# 2024-08-19.net
KiCad netlist of a schematic drawn in Altium Designer
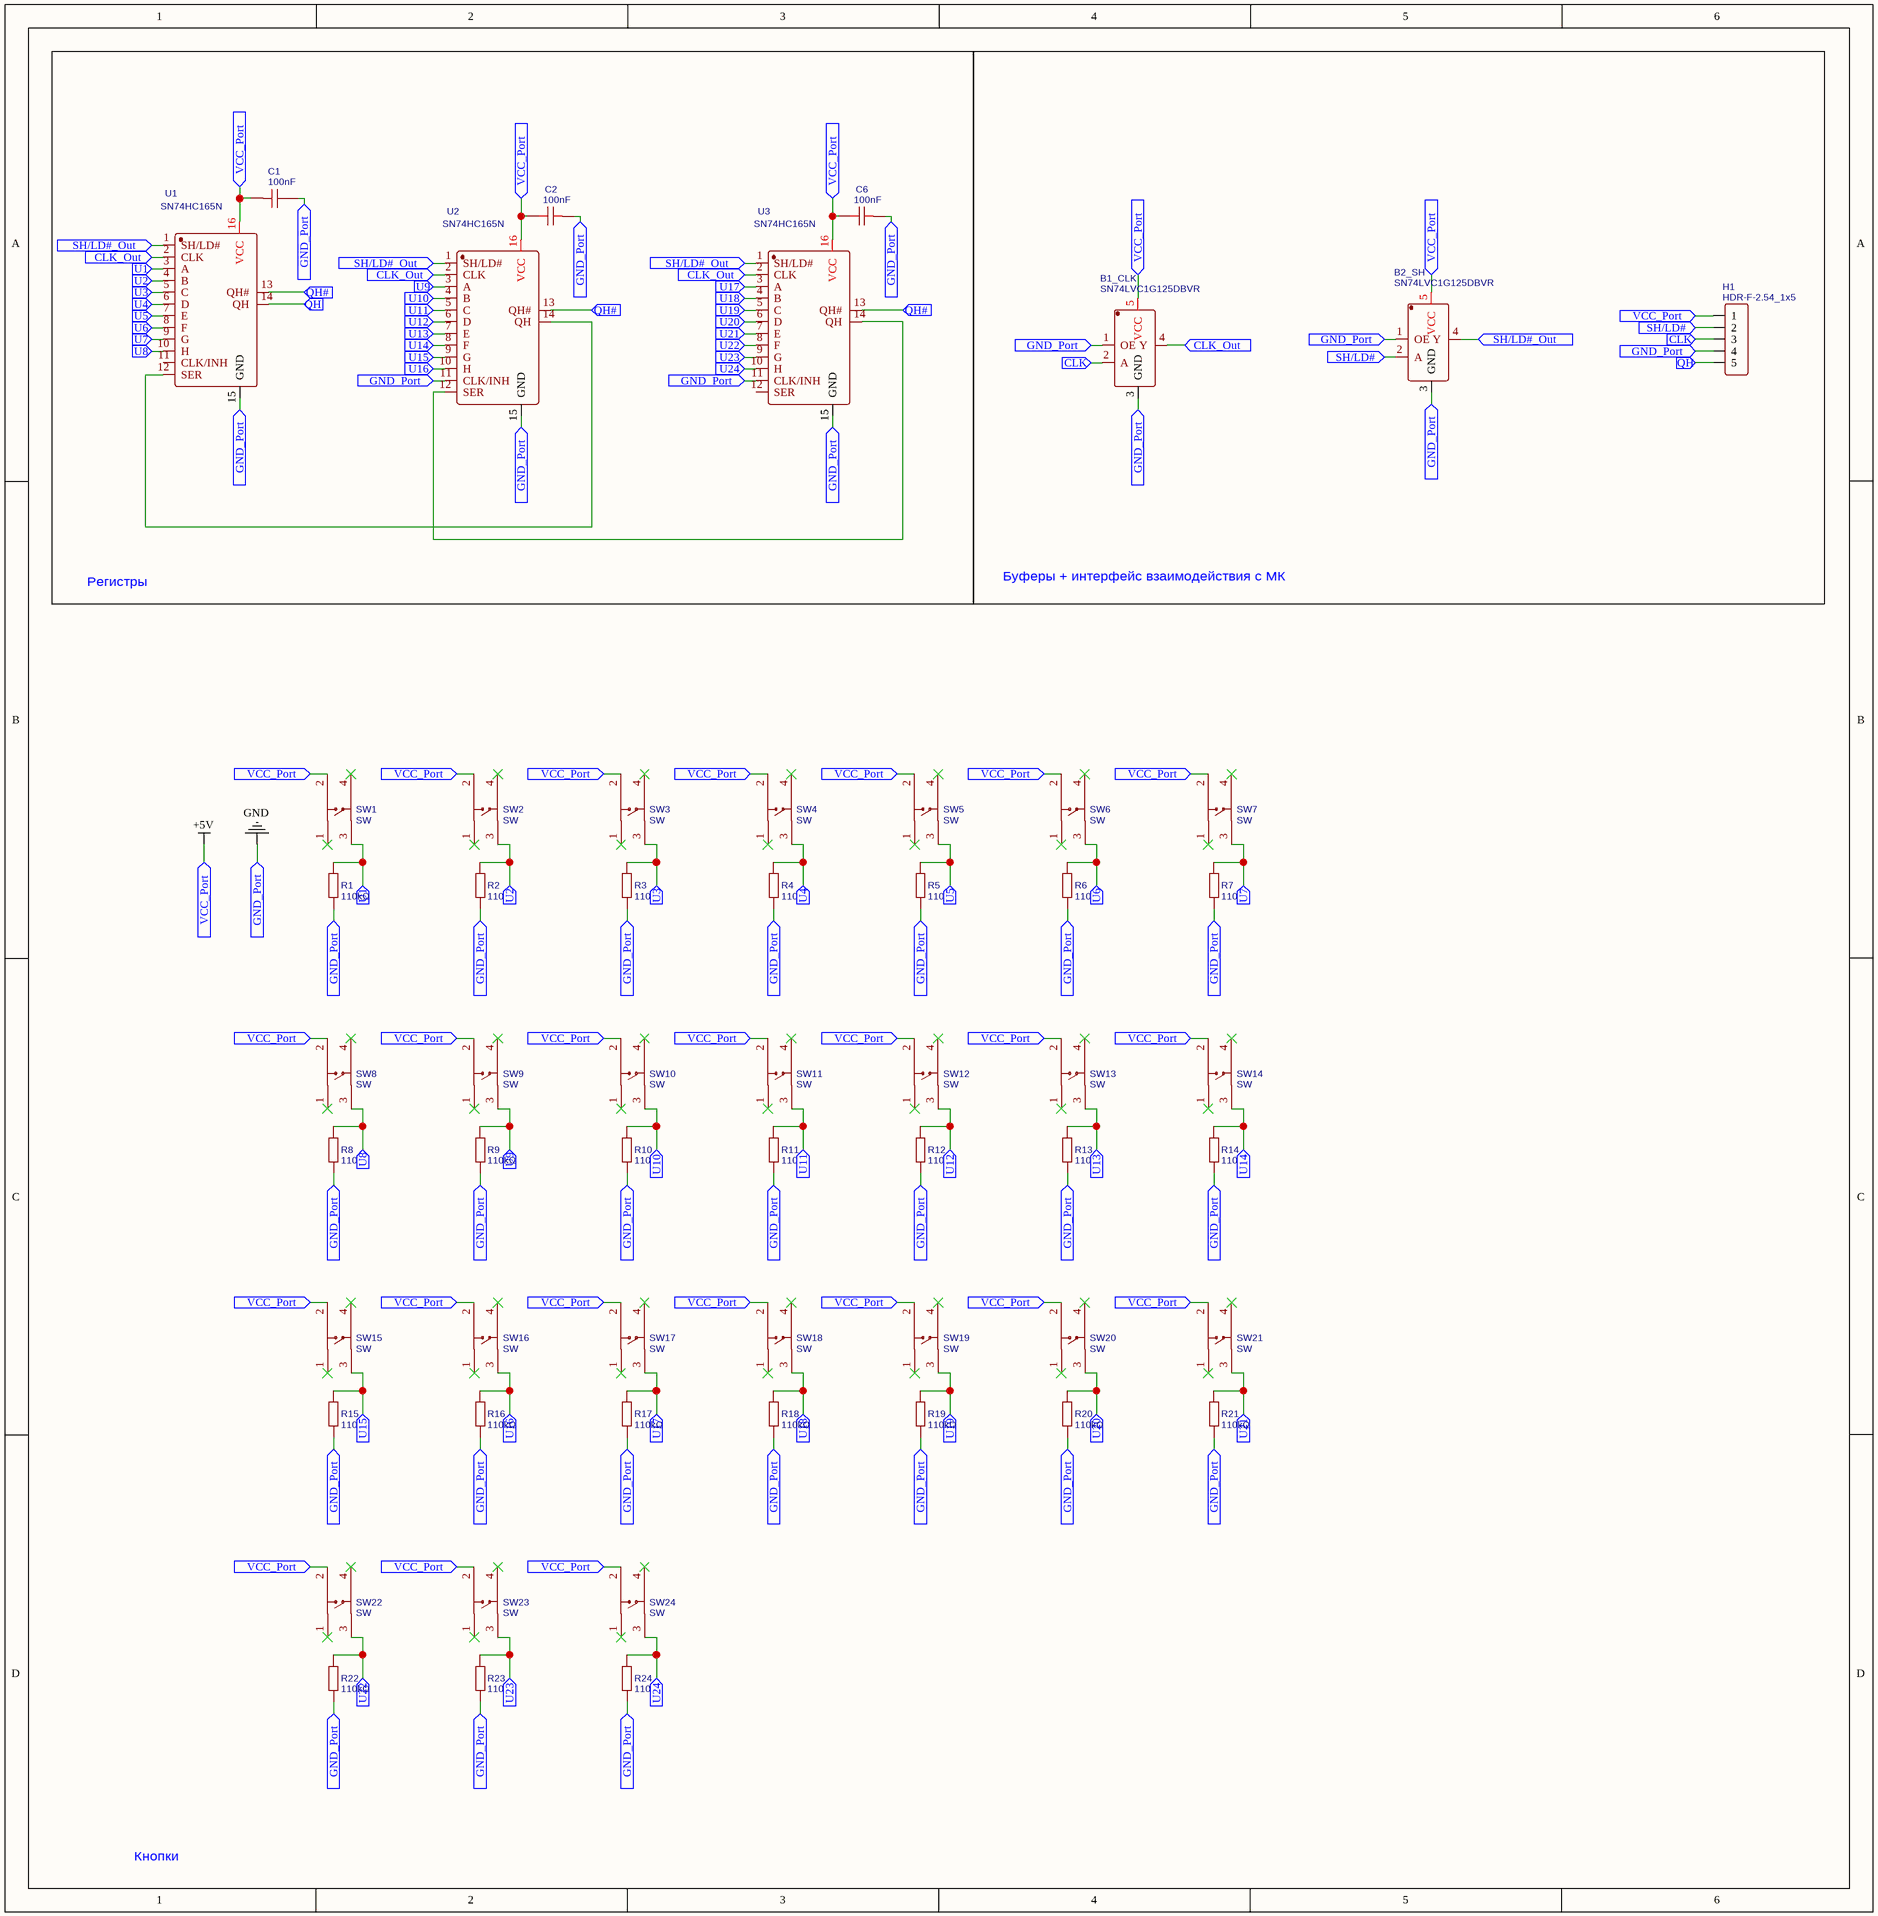
[diagram p0: Кнопки_2024-08-19.schdoc]

(export (version "E")
  (design (tool "Eeschema 10.0.6"))
  (components
    (comp (ref "B1_CLK")
      (value "SN74LVC1G125DBVR")
      (fields (field (name "MANUFACTURER") "TI(德州仪器)") (field (name "CONTRIBUTOR") "danik_mus"))
      (libsource (lib "altium-import") (part "root_0_SN74LVC1G125DBVR_"))
    )
    (comp (ref "B2_SH")
      (value "SN74LVC1G125DBVR")
      (fields (field (name "MANUFACTURER") "TI(德州仪器)") (field (name "CONTRIBUTOR") "danik_mus"))
      (libsource (lib "altium-import") (part "root_0_SN74LVC1G125DBVR_"))
    )
    (comp (ref "C1")
      (value "100nF")
      (fields
        (field (name "MANUFACTURER") "KYET(科雅)")
        (field (name "MANUFACTURER PART") "PE104J2A0504")
        (field (name "CONTRIBUTOR") "lcsc")
      )
      (libsource (lib "altium-import") (part "root_0_100nF_"))
    )
    (comp (ref "C2")
      (value "100nF")
      (fields
        (field (name "MANUFACTURER") "KYET(科雅)")
        (field (name "MANUFACTURER PART") "PE104J2A0504")
        (field (name "CONTRIBUTOR") "lcsc")
      )
      (libsource (lib "altium-import") (part "root_2_100nF_"))
    )
    (comp (ref "C6")
      (value "100nF")
      (fields
        (field (name "MANUFACTURER") "KYET(科雅)")
        (field (name "MANUFACTURER PART") "PE104J2A0504")
        (field (name "CONTRIBUTOR") "lcsc")
      )
      (libsource (lib "altium-import") (part "root_2_100nF_"))
    )
    (comp (ref "H1")
      (value "HDR-F-2.54_1x5")
      (fields (field (name "CONTRIBUTOR") "LCEDA_Lib"))
      (libsource (lib "altium-import") (part "root_0_HDR-F-2.54_1x5_"))
    )
    (comp (ref "R1")
      (value "110kΩ")
      (fields
        (field (name "MANUFACTURER") "CCO(千志电子)")
        (field (name "MANUFACTURER PART") "CF1/4W-110KΩ±5% T52")
        (field (name "CONTRIBUTOR") "LCSC")
      )
      (libsource (lib "altium-import") (part "root_3_110kΩ_"))
    )
    (comp (ref "R2")
      (value "110kΩ")
      (fields
        (field (name "MANUFACTURER") "CCO(千志电子)")
        (field (name "MANUFACTURER PART") "CF1/4W-110KΩ±5% T52")
        (field (name "CONTRIBUTOR") "LCSC")
      )
      (libsource (lib "altium-import") (part "root_3_110kΩ_"))
    )
    (comp (ref "R3")
      (value "110kΩ")
      (fields
        (field (name "MANUFACTURER") "CCO(千志电子)")
        (field (name "MANUFACTURER PART") "CF1/4W-110KΩ±5% T52")
        (field (name "CONTRIBUTOR") "LCSC")
      )
      (libsource (lib "altium-import") (part "root_3_110kΩ_"))
    )
    (comp (ref "R4")
      (value "110kΩ")
      (fields
        (field (name "MANUFACTURER") "CCO(千志电子)")
        (field (name "MANUFACTURER PART") "CF1/4W-110KΩ±5% T52")
        (field (name "CONTRIBUTOR") "LCSC")
      )
      (libsource (lib "altium-import") (part "root_3_110kΩ_"))
    )
    (comp (ref "R5")
      (value "110kΩ")
      (fields
        (field (name "MANUFACTURER") "CCO(千志电子)")
        (field (name "MANUFACTURER PART") "CF1/4W-110KΩ±5% T52")
        (field (name "CONTRIBUTOR") "LCSC")
      )
      (libsource (lib "altium-import") (part "root_3_110kΩ_"))
    )
    (comp (ref "R6")
      (value "110kΩ")
      (fields
        (field (name "MANUFACTURER") "CCO(千志电子)")
        (field (name "MANUFACTURER PART") "CF1/4W-110KΩ±5% T52")
        (field (name "CONTRIBUTOR") "LCSC")
      )
      (libsource (lib "altium-import") (part "root_3_110kΩ_"))
    )
    (comp (ref "R7")
      (value "110kΩ")
      (fields
        (field (name "MANUFACTURER") "CCO(千志电子)")
        (field (name "MANUFACTURER PART") "CF1/4W-110KΩ±5% T52")
        (field (name "CONTRIBUTOR") "LCSC")
      )
      (libsource (lib "altium-import") (part "root_3_110kΩ_"))
    )
    (comp (ref "R8")
      (value "110kΩ")
      (fields
        (field (name "MANUFACTURER") "CCO(千志电子)")
        (field (name "MANUFACTURER PART") "CF1/4W-110KΩ±5% T52")
        (field (name "CONTRIBUTOR") "LCSC")
      )
      (libsource (lib "altium-import") (part "root_3_110kΩ_"))
    )
    (comp (ref "R9")
      (value "110kΩ")
      (fields
        (field (name "MANUFACTURER") "CCO(千志电子)")
        (field (name "MANUFACTURER PART") "CF1/4W-110KΩ±5% T52")
        (field (name "CONTRIBUTOR") "LCSC")
      )
      (libsource (lib "altium-import") (part "root_3_110kΩ_"))
    )
    (comp (ref "R10")
      (value "110kΩ")
      (fields
        (field (name "MANUFACTURER") "CCO(千志电子)")
        (field (name "MANUFACTURER PART") "CF1/4W-110KΩ±5% T52")
        (field (name "CONTRIBUTOR") "LCSC")
      )
      (libsource (lib "altium-import") (part "root_3_110kΩ_"))
    )
    (comp (ref "R11")
      (value "110kΩ")
      (fields
        (field (name "MANUFACTURER") "CCO(千志电子)")
        (field (name "MANUFACTURER PART") "CF1/4W-110KΩ±5% T52")
        (field (name "CONTRIBUTOR") "LCSC")
      )
      (libsource (lib "altium-import") (part "root_3_110kΩ_"))
    )
    (comp (ref "R12")
      (value "110kΩ")
      (fields
        (field (name "MANUFACTURER") "CCO(千志电子)")
        (field (name "MANUFACTURER PART") "CF1/4W-110KΩ±5% T52")
        (field (name "CONTRIBUTOR") "LCSC")
      )
      (libsource (lib "altium-import") (part "root_3_110kΩ_"))
    )
    (comp (ref "R13")
      (value "110kΩ")
      (fields
        (field (name "MANUFACTURER") "CCO(千志电子)")
        (field (name "MANUFACTURER PART") "CF1/4W-110KΩ±5% T52")
        (field (name "CONTRIBUTOR") "LCSC")
      )
      (libsource (lib "altium-import") (part "root_3_110kΩ_"))
    )
    (comp (ref "R14")
      (value "110kΩ")
      (fields
        (field (name "MANUFACTURER") "CCO(千志电子)")
        (field (name "MANUFACTURER PART") "CF1/4W-110KΩ±5% T52")
        (field (name "CONTRIBUTOR") "LCSC")
      )
      (libsource (lib "altium-import") (part "root_3_110kΩ_"))
    )
    (comp (ref "R15")
      (value "110kΩ")
      (fields
        (field (name "MANUFACTURER") "CCO(千志电子)")
        (field (name "MANUFACTURER PART") "CF1/4W-110KΩ±5% T52")
        (field (name "CONTRIBUTOR") "LCSC")
      )
      (libsource (lib "altium-import") (part "root_3_110kΩ_"))
    )
    (comp (ref "R16")
      (value "110kΩ")
      (fields
        (field (name "MANUFACTURER") "CCO(千志电子)")
        (field (name "MANUFACTURER PART") "CF1/4W-110KΩ±5% T52")
        (field (name "CONTRIBUTOR") "LCSC")
      )
      (libsource (lib "altium-import") (part "root_3_110kΩ_"))
    )
    (comp (ref "R17")
      (value "110kΩ")
      (fields
        (field (name "MANUFACTURER") "CCO(千志电子)")
        (field (name "MANUFACTURER PART") "CF1/4W-110KΩ±5% T52")
        (field (name "CONTRIBUTOR") "LCSC")
      )
      (libsource (lib "altium-import") (part "root_3_110kΩ_"))
    )
    (comp (ref "R18")
      (value "110kΩ")
      (fields
        (field (name "MANUFACTURER") "CCO(千志电子)")
        (field (name "MANUFACTURER PART") "CF1/4W-110KΩ±5% T52")
        (field (name "CONTRIBUTOR") "LCSC")
      )
      (libsource (lib "altium-import") (part "root_3_110kΩ_"))
    )
    (comp (ref "R19")
      (value "110kΩ")
      (fields
        (field (name "MANUFACTURER") "CCO(千志电子)")
        (field (name "MANUFACTURER PART") "CF1/4W-110KΩ±5% T52")
        (field (name "CONTRIBUTOR") "LCSC")
      )
      (libsource (lib "altium-import") (part "root_3_110kΩ_"))
    )
    (comp (ref "R20")
      (value "110kΩ")
      (fields
        (field (name "MANUFACTURER") "CCO(千志电子)")
        (field (name "MANUFACTURER PART") "CF1/4W-110KΩ±5% T52")
        (field (name "CONTRIBUTOR") "LCSC")
      )
      (libsource (lib "altium-import") (part "root_3_110kΩ_"))
    )
    (comp (ref "R21")
      (value "110kΩ")
      (fields
        (field (name "MANUFACTURER") "CCO(千志电子)")
        (field (name "MANUFACTURER PART") "CF1/4W-110KΩ±5% T52")
        (field (name "CONTRIBUTOR") "LCSC")
      )
      (libsource (lib "altium-import") (part "root_3_110kΩ_"))
    )
    (comp (ref "R22")
      (value "110kΩ")
      (fields
        (field (name "MANUFACTURER") "CCO(千志电子)")
        (field (name "MANUFACTURER PART") "CF1/4W-110KΩ±5% T52")
        (field (name "CONTRIBUTOR") "LCSC")
      )
      (libsource (lib "altium-import") (part "root_3_110kΩ_"))
    )
    (comp (ref "R23")
      (value "110kΩ")
      (fields
        (field (name "MANUFACTURER") "CCO(千志电子)")
        (field (name "MANUFACTURER PART") "CF1/4W-110KΩ±5% T52")
        (field (name "CONTRIBUTOR") "LCSC")
      )
      (libsource (lib "altium-import") (part "root_3_110kΩ_"))
    )
    (comp (ref "R24")
      (value "110kΩ")
      (fields
        (field (name "MANUFACTURER") "CCO(千志电子)")
        (field (name "MANUFACTURER PART") "CF1/4W-110KΩ±5% T52")
        (field (name "CONTRIBUTOR") "LCSC")
      )
      (libsource (lib "altium-import") (part "root_3_110kΩ_"))
    )
    (comp (ref "SW1")
      (value "SW")
      (fields (field (name "MANUFACTURER PART") "按键") (field (name "CONTRIBUTOR") "lcsc"))
      (libsource (lib "altium-import") (part "root_1_SW_"))
    )
    (comp (ref "SW2")
      (value "SW")
      (fields (field (name "MANUFACTURER PART") "按键") (field (name "CONTRIBUTOR") "lcsc"))
      (libsource (lib "altium-import") (part "root_1_SW_"))
    )
    (comp (ref "SW3")
      (value "SW")
      (fields (field (name "MANUFACTURER PART") "按键") (field (name "CONTRIBUTOR") "lcsc"))
      (libsource (lib "altium-import") (part "root_1_SW_"))
    )
    (comp (ref "SW4")
      (value "SW")
      (fields (field (name "MANUFACTURER PART") "按键") (field (name "CONTRIBUTOR") "lcsc"))
      (libsource (lib "altium-import") (part "root_1_SW_"))
    )
    (comp (ref "SW5")
      (value "SW")
      (fields (field (name "MANUFACTURER PART") "按键") (field (name "CONTRIBUTOR") "lcsc"))
      (libsource (lib "altium-import") (part "root_1_SW_"))
    )
    (comp (ref "SW6")
      (value "SW")
      (fields (field (name "MANUFACTURER PART") "按键") (field (name "CONTRIBUTOR") "lcsc"))
      (libsource (lib "altium-import") (part "root_1_SW_"))
    )
    (comp (ref "SW7")
      (value "SW")
      (fields (field (name "MANUFACTURER PART") "按键") (field (name "CONTRIBUTOR") "lcsc"))
      (libsource (lib "altium-import") (part "root_1_SW_"))
    )
    (comp (ref "SW8")
      (value "SW")
      (fields (field (name "MANUFACTURER PART") "按键") (field (name "CONTRIBUTOR") "lcsc"))
      (libsource (lib "altium-import") (part "root_1_SW_"))
    )
    (comp (ref "SW9")
      (value "SW")
      (fields (field (name "MANUFACTURER PART") "按键") (field (name "CONTRIBUTOR") "lcsc"))
      (libsource (lib "altium-import") (part "root_1_SW_"))
    )
    (comp (ref "SW10")
      (value "SW")
      (fields (field (name "MANUFACTURER PART") "按键") (field (name "CONTRIBUTOR") "lcsc"))
      (libsource (lib "altium-import") (part "root_1_SW_"))
    )
    (comp (ref "SW11")
      (value "SW")
      (fields (field (name "MANUFACTURER PART") "按键") (field (name "CONTRIBUTOR") "lcsc"))
      (libsource (lib "altium-import") (part "root_1_SW_"))
    )
    (comp (ref "SW12")
      (value "SW")
      (fields (field (name "MANUFACTURER PART") "按键") (field (name "CONTRIBUTOR") "lcsc"))
      (libsource (lib "altium-import") (part "root_1_SW_"))
    )
    (comp (ref "SW13")
      (value "SW")
      (fields (field (name "MANUFACTURER PART") "按键") (field (name "CONTRIBUTOR") "lcsc"))
      (libsource (lib "altium-import") (part "root_1_SW_"))
    )
    (comp (ref "SW14")
      (value "SW")
      (fields (field (name "MANUFACTURER PART") "按键") (field (name "CONTRIBUTOR") "lcsc"))
      (libsource (lib "altium-import") (part "root_1_SW_"))
    )
    (comp (ref "SW15")
      (value "SW")
      (fields (field (name "MANUFACTURER PART") "按键") (field (name "CONTRIBUTOR") "lcsc"))
      (libsource (lib "altium-import") (part "root_1_SW_"))
    )
    (comp (ref "SW16")
      (value "SW")
      (fields (field (name "MANUFACTURER PART") "按键") (field (name "CONTRIBUTOR") "lcsc"))
      (libsource (lib "altium-import") (part "root_1_SW_"))
    )
    (comp (ref "SW17")
      (value "SW")
      (fields (field (name "MANUFACTURER PART") "按键") (field (name "CONTRIBUTOR") "lcsc"))
      (libsource (lib "altium-import") (part "root_1_SW_"))
    )
    (comp (ref "SW18")
      (value "SW")
      (fields (field (name "MANUFACTURER PART") "按键") (field (name "CONTRIBUTOR") "lcsc"))
      (libsource (lib "altium-import") (part "root_1_SW_"))
    )
    (comp (ref "SW19")
      (value "SW")
      (fields (field (name "MANUFACTURER PART") "按键") (field (name "CONTRIBUTOR") "lcsc"))
      (libsource (lib "altium-import") (part "root_1_SW_"))
    )
    (comp (ref "SW20")
      (value "SW")
      (fields (field (name "MANUFACTURER PART") "按键") (field (name "CONTRIBUTOR") "lcsc"))
      (libsource (lib "altium-import") (part "root_1_SW_"))
    )
    (comp (ref "SW21")
      (value "SW")
      (fields (field (name "MANUFACTURER PART") "按键") (field (name "CONTRIBUTOR") "lcsc"))
      (libsource (lib "altium-import") (part "root_1_SW_"))
    )
    (comp (ref "SW22")
      (value "SW")
      (fields (field (name "MANUFACTURER PART") "按键") (field (name "CONTRIBUTOR") "lcsc"))
      (libsource (lib "altium-import") (part "root_1_SW_"))
    )
    (comp (ref "SW23")
      (value "SW")
      (fields (field (name "MANUFACTURER PART") "按键") (field (name "CONTRIBUTOR") "lcsc"))
      (libsource (lib "altium-import") (part "root_1_SW_"))
    )
    (comp (ref "SW24")
      (value "SW")
      (fields (field (name "MANUFACTURER PART") "按键") (field (name "CONTRIBUTOR") "lcsc"))
      (libsource (lib "altium-import") (part "root_1_SW_"))
    )
    (comp (ref "U1")
      (value "SN74HC165N")
      (fields (field (name "MANUFACTURER") "TI(德州仪器)") (field (name "CONTRIBUTOR") "danik_mus"))
      (libsource (lib "altium-import") (part "root_0_SN74HC165N_"))
    )
    (comp (ref "U2")
      (value "SN74HC165N")
      (fields (field (name "MANUFACTURER") "TI(德州仪器)") (field (name "CONTRIBUTOR") "danik_mus"))
      (libsource (lib "altium-import") (part "root_0_SN74HC165N_"))
    )
    (comp (ref "U3")
      (value "SN74HC165N")
      (fields (field (name "MANUFACTURER") "TI(德州仪器)") (field (name "CONTRIBUTOR") "danik_mus"))
      (libsource (lib "altium-import") (part "root_0_SN74HC165N_"))
    )
  )
  (nets
    (net (code "1") (name "+5V") (class "Default")
      (node (ref "B1_CLK") (pin "5") (pinfunction "VCC_5") (pintype "passive"))
      (node (ref "B2_SH") (pin "5") (pinfunction "VCC_5") (pintype "passive"))
      (node (ref "C1") (pin "1") (pinfunction "1_1") (pintype "passive"))
      (node (ref "C2") (pin "2") (pinfunction "2_2") (pintype "passive"))
      (node (ref "C6") (pin "2") (pinfunction "2_2") (pintype "passive"))
      (node (ref "H1") (pin "1") (pinfunction "1_1") (pintype "passive"))
      (node (ref "SW1") (pin "2") (pinfunction "2_2") (pintype "passive"))
      (node (ref "SW10") (pin "2") (pinfunction "2_2") (pintype "passive"))
      (node (ref "SW11") (pin "2") (pinfunction "2_2") (pintype "passive"))
      (node (ref "SW12") (pin "2") (pinfunction "2_2") (pintype "passive"))
      (node (ref "SW13") (pin "2") (pinfunction "2_2") (pintype "passive"))
      (node (ref "SW14") (pin "2") (pinfunction "2_2") (pintype "passive"))
      (node (ref "SW15") (pin "2") (pinfunction "2_2") (pintype "passive"))
      (node (ref "SW16") (pin "2") (pinfunction "2_2") (pintype "passive"))
      (node (ref "SW17") (pin "2") (pinfunction "2_2") (pintype "passive"))
      (node (ref "SW18") (pin "2") (pinfunction "2_2") (pintype "passive"))
      (node (ref "SW19") (pin "2") (pinfunction "2_2") (pintype "passive"))
      (node (ref "SW2") (pin "2") (pinfunction "2_2") (pintype "passive"))
      (node (ref "SW20") (pin "2") (pinfunction "2_2") (pintype "passive"))
      (node (ref "SW21") (pin "2") (pinfunction "2_2") (pintype "passive"))
      (node (ref "SW22") (pin "2") (pinfunction "2_2") (pintype "passive"))
      (node (ref "SW23") (pin "2") (pinfunction "2_2") (pintype "passive"))
      (node (ref "SW24") (pin "2") (pinfunction "2_2") (pintype "passive"))
      (node (ref "SW3") (pin "2") (pinfunction "2_2") (pintype "passive"))
      (node (ref "SW4") (pin "2") (pinfunction "2_2") (pintype "passive"))
      (node (ref "SW5") (pin "2") (pinfunction "2_2") (pintype "passive"))
      (node (ref "SW6") (pin "2") (pinfunction "2_2") (pintype "passive"))
      (node (ref "SW7") (pin "2") (pinfunction "2_2") (pintype "passive"))
      (node (ref "SW8") (pin "2") (pinfunction "2_2") (pintype "passive"))
      (node (ref "SW9") (pin "2") (pinfunction "2_2") (pintype "passive"))
      (node (ref "U1") (pin "16") (pinfunction "VCC_16") (pintype "passive"))
      (node (ref "U2") (pin "16") (pinfunction "VCC_16") (pintype "passive"))
      (node (ref "U3") (pin "16") (pinfunction "VCC_16") (pintype "passive"))
    )
    (net (code "2") (name "/CLK") (class "Default")
      (node (ref "B1_CLK") (pin "2") (pinfunction "A_2") (pintype "passive"))
      (node (ref "H1") (pin "3") (pinfunction "3_3") (pintype "passive"))
    )
    (net (code "3") (name "/CLK_Out") (class "Default")
      (node (ref "B1_CLK") (pin "4") (pinfunction "Y_4") (pintype "passive"))
      (node (ref "U1") (pin "2") (pinfunction "CLK_2") (pintype "passive"))
      (node (ref "U2") (pin "2") (pinfunction "CLK_2") (pintype "passive"))
      (node (ref "U3") (pin "2") (pinfunction "CLK_2") (pintype "passive"))
    )
    (net (code "4") (name "/QH") (class "Default")
      (node (ref "H1") (pin "5") (pinfunction "5_5") (pintype "passive"))
      (node (ref "U1") (pin "14") (pinfunction "QH_14") (pintype "passive"))
    )
    (net (code "5") (name "/QH#") (class "Default")
      (node (ref "U1") (pin "13") (pinfunction "QH#_13") (pintype "passive"))
      (node (ref "U2") (pin "13") (pinfunction "QH#_13") (pintype "passive"))
      (node (ref "U3") (pin "13") (pinfunction "QH#_13") (pintype "passive"))
    )
    (net (code "6") (name "/SH{slash}LD#") (class "Default")
      (node (ref "B2_SH") (pin "2") (pinfunction "A_2") (pintype "passive"))
      (node (ref "H1") (pin "2") (pinfunction "2_2") (pintype "passive"))
    )
    (net (code "7") (name "/SH{slash}LD#_Out") (class "Default")
      (node (ref "B2_SH") (pin "4") (pinfunction "Y_4") (pintype "passive"))
      (node (ref "U1") (pin "1") (pinfunction "SH/LD#_1") (pintype "passive"))
      (node (ref "U2") (pin "1") (pinfunction "SH/LD#_1") (pintype "passive"))
      (node (ref "U3") (pin "1") (pinfunction "SH/LD#_1") (pintype "passive"))
    )
    (net (code "8") (name "/U1") (class "Default")
      (node (ref "R1") (pin "1") (pinfunction "1_1") (pintype "passive"))
      (node (ref "SW1") (pin "3") (pinfunction "3_3") (pintype "passive"))
      (node (ref "U1") (pin "3") (pinfunction "A_3") (pintype "passive"))
    )
    (net (code "9") (name "/U2") (class "Default")
      (node (ref "R2") (pin "1") (pinfunction "1_1") (pintype "passive"))
      (node (ref "SW2") (pin "3") (pinfunction "3_3") (pintype "passive"))
      (node (ref "U1") (pin "4") (pinfunction "B_4") (pintype "passive"))
    )
    (net (code "10") (name "/U3") (class "Default")
      (node (ref "R3") (pin "1") (pinfunction "1_1") (pintype "passive"))
      (node (ref "SW3") (pin "3") (pinfunction "3_3") (pintype "passive"))
      (node (ref "U1") (pin "5") (pinfunction "C_5") (pintype "passive"))
    )
    (net (code "11") (name "/U4") (class "Default")
      (node (ref "R4") (pin "1") (pinfunction "1_1") (pintype "passive"))
      (node (ref "SW4") (pin "3") (pinfunction "3_3") (pintype "passive"))
      (node (ref "U1") (pin "6") (pinfunction "D_6") (pintype "passive"))
    )
    (net (code "12") (name "/U5") (class "Default")
      (node (ref "R5") (pin "1") (pinfunction "1_1") (pintype "passive"))
      (node (ref "SW5") (pin "3") (pinfunction "3_3") (pintype "passive"))
      (node (ref "U1") (pin "7") (pinfunction "E_7") (pintype "passive"))
    )
    (net (code "13") (name "/U6") (class "Default")
      (node (ref "R6") (pin "1") (pinfunction "1_1") (pintype "passive"))
      (node (ref "SW6") (pin "3") (pinfunction "3_3") (pintype "passive"))
      (node (ref "U1") (pin "8") (pinfunction "F_8") (pintype "passive"))
    )
    (net (code "14") (name "/U7") (class "Default")
      (node (ref "R7") (pin "1") (pinfunction "1_1") (pintype "passive"))
      (node (ref "SW7") (pin "3") (pinfunction "3_3") (pintype "passive"))
      (node (ref "U1") (pin "9") (pinfunction "G_9") (pintype "passive"))
    )
    (net (code "15") (name "/U8") (class "Default")
      (node (ref "R8") (pin "1") (pinfunction "1_1") (pintype "passive"))
      (node (ref "SW8") (pin "3") (pinfunction "3_3") (pintype "passive"))
      (node (ref "U1") (pin "10") (pinfunction "H_10") (pintype "passive"))
    )
    (net (code "16") (name "/U9") (class "Default")
      (node (ref "R9") (pin "1") (pinfunction "1_1") (pintype "passive"))
      (node (ref "SW9") (pin "3") (pinfunction "3_3") (pintype "passive"))
      (node (ref "U2") (pin "3") (pinfunction "A_3") (pintype "passive"))
    )
    (net (code "17") (name "/U10") (class "Default")
      (node (ref "R10") (pin "1") (pinfunction "1_1") (pintype "passive"))
      (node (ref "SW10") (pin "3") (pinfunction "3_3") (pintype "passive"))
      (node (ref "U2") (pin "4") (pinfunction "B_4") (pintype "passive"))
    )
    (net (code "18") (name "/U11") (class "Default")
      (node (ref "R11") (pin "1") (pinfunction "1_1") (pintype "passive"))
      (node (ref "SW11") (pin "3") (pinfunction "3_3") (pintype "passive"))
      (node (ref "U2") (pin "5") (pinfunction "C_5") (pintype "passive"))
    )
    (net (code "19") (name "/U12") (class "Default")
      (node (ref "R12") (pin "1") (pinfunction "1_1") (pintype "passive"))
      (node (ref "SW12") (pin "3") (pinfunction "3_3") (pintype "passive"))
      (node (ref "U2") (pin "6") (pinfunction "D_6") (pintype "passive"))
    )
    (net (code "20") (name "/U13") (class "Default")
      (node (ref "R13") (pin "1") (pinfunction "1_1") (pintype "passive"))
      (node (ref "SW13") (pin "3") (pinfunction "3_3") (pintype "passive"))
      (node (ref "U2") (pin "7") (pinfunction "E_7") (pintype "passive"))
    )
    (net (code "21") (name "/U14") (class "Default")
      (node (ref "R14") (pin "1") (pinfunction "1_1") (pintype "passive"))
      (node (ref "SW14") (pin "3") (pinfunction "3_3") (pintype "passive"))
      (node (ref "U2") (pin "8") (pinfunction "F_8") (pintype "passive"))
    )
    (net (code "22") (name "/U15") (class "Default")
      (node (ref "R15") (pin "1") (pinfunction "1_1") (pintype "passive"))
      (node (ref "SW15") (pin "3") (pinfunction "3_3") (pintype "passive"))
      (node (ref "U2") (pin "9") (pinfunction "G_9") (pintype "passive"))
    )
    (net (code "23") (name "/U16") (class "Default")
      (node (ref "R16") (pin "1") (pinfunction "1_1") (pintype "passive"))
      (node (ref "SW16") (pin "3") (pinfunction "3_3") (pintype "passive"))
      (node (ref "U2") (pin "10") (pinfunction "H_10") (pintype "passive"))
    )
    (net (code "24") (name "/U17") (class "Default")
      (node (ref "R17") (pin "1") (pinfunction "1_1") (pintype "passive"))
      (node (ref "SW17") (pin "3") (pinfunction "3_3") (pintype "passive"))
      (node (ref "U3") (pin "3") (pinfunction "A_3") (pintype "passive"))
    )
    (net (code "25") (name "/U18") (class "Default")
      (node (ref "R18") (pin "1") (pinfunction "1_1") (pintype "passive"))
      (node (ref "SW18") (pin "3") (pinfunction "3_3") (pintype "passive"))
      (node (ref "U3") (pin "4") (pinfunction "B_4") (pintype "passive"))
    )
    (net (code "26") (name "/U19") (class "Default")
      (node (ref "R19") (pin "1") (pinfunction "1_1") (pintype "passive"))
      (node (ref "SW19") (pin "3") (pinfunction "3_3") (pintype "passive"))
      (node (ref "U3") (pin "5") (pinfunction "C_5") (pintype "passive"))
    )
    (net (code "27") (name "/U20") (class "Default")
      (node (ref "R20") (pin "1") (pinfunction "1_1") (pintype "passive"))
      (node (ref "SW20") (pin "3") (pinfunction "3_3") (pintype "passive"))
      (node (ref "U3") (pin "6") (pinfunction "D_6") (pintype "passive"))
    )
    (net (code "28") (name "/U21") (class "Default")
      (node (ref "R21") (pin "1") (pinfunction "1_1") (pintype "passive"))
      (node (ref "SW21") (pin "3") (pinfunction "3_3") (pintype "passive"))
      (node (ref "U3") (pin "7") (pinfunction "E_7") (pintype "passive"))
    )
    (net (code "29") (name "/U22") (class "Default")
      (node (ref "R22") (pin "1") (pinfunction "1_1") (pintype "passive"))
      (node (ref "SW22") (pin "3") (pinfunction "3_3") (pintype "passive"))
      (node (ref "U3") (pin "8") (pinfunction "F_8") (pintype "passive"))
    )
    (net (code "30") (name "/U23") (class "Default")
      (node (ref "R23") (pin "1") (pinfunction "1_1") (pintype "passive"))
      (node (ref "SW23") (pin "3") (pinfunction "3_3") (pintype "passive"))
      (node (ref "U3") (pin "9") (pinfunction "G_9") (pintype "passive"))
    )
    (net (code "31") (name "/U24") (class "Default")
      (node (ref "R24") (pin "1") (pinfunction "1_1") (pintype "passive"))
      (node (ref "SW24") (pin "3") (pinfunction "3_3") (pintype "passive"))
      (node (ref "U3") (pin "10") (pinfunction "H_10") (pintype "passive"))
    )
    (net (code "32") (name "GND") (class "Default")
      (node (ref "B1_CLK") (pin "1") (pinfunction "OE_1") (pintype "passive"))
      (node (ref "B1_CLK") (pin "3") (pinfunction "GND_3") (pintype "passive"))
      (node (ref "B2_SH") (pin "1") (pinfunction "OE_1") (pintype "passive"))
      (node (ref "B2_SH") (pin "3") (pinfunction "GND_3") (pintype "passive"))
      (node (ref "C1") (pin "2") (pinfunction "2_2") (pintype "passive"))
      (node (ref "C2") (pin "1") (pinfunction "1_1") (pintype "passive"))
      (node (ref "C6") (pin "1") (pinfunction "1_1") (pintype "passive"))
      (node (ref "H1") (pin "4") (pinfunction "4_4") (pintype "passive"))
      (node (ref "R1") (pin "2") (pinfunction "2_2") (pintype "passive"))
      (node (ref "R10") (pin "2") (pinfunction "2_2") (pintype "passive"))
      (node (ref "R11") (pin "2") (pinfunction "2_2") (pintype "passive"))
      (node (ref "R12") (pin "2") (pinfunction "2_2") (pintype "passive"))
      (node (ref "R13") (pin "2") (pinfunction "2_2") (pintype "passive"))
      (node (ref "R14") (pin "2") (pinfunction "2_2") (pintype "passive"))
      (node (ref "R15") (pin "2") (pinfunction "2_2") (pintype "passive"))
      (node (ref "R16") (pin "2") (pinfunction "2_2") (pintype "passive"))
      (node (ref "R17") (pin "2") (pinfunction "2_2") (pintype "passive"))
      (node (ref "R18") (pin "2") (pinfunction "2_2") (pintype "passive"))
      (node (ref "R19") (pin "2") (pinfunction "2_2") (pintype "passive"))
      (node (ref "R2") (pin "2") (pinfunction "2_2") (pintype "passive"))
      (node (ref "R20") (pin "2") (pinfunction "2_2") (pintype "passive"))
      (node (ref "R21") (pin "2") (pinfunction "2_2") (pintype "passive"))
      (node (ref "R22") (pin "2") (pinfunction "2_2") (pintype "passive"))
      (node (ref "R23") (pin "2") (pinfunction "2_2") (pintype "passive"))
      (node (ref "R24") (pin "2") (pinfunction "2_2") (pintype "passive"))
      (node (ref "R3") (pin "2") (pinfunction "2_2") (pintype "passive"))
      (node (ref "R4") (pin "2") (pinfunction "2_2") (pintype "passive"))
      (node (ref "R5") (pin "2") (pinfunction "2_2") (pintype "passive"))
      (node (ref "R6") (pin "2") (pinfunction "2_2") (pintype "passive"))
      (node (ref "R7") (pin "2") (pinfunction "2_2") (pintype "passive"))
      (node (ref "R8") (pin "2") (pinfunction "2_2") (pintype "passive"))
      (node (ref "R9") (pin "2") (pinfunction "2_2") (pintype "passive"))
      (node (ref "U1") (pin "15") (pinfunction "GND_15") (pintype "passive"))
      (node (ref "U2") (pin "11") (pinfunction "CLK/INH_11") (pintype "passive"))
      (node (ref "U2") (pin "15") (pinfunction "GND_15") (pintype "passive"))
      (node (ref "U3") (pin "11") (pinfunction "CLK/INH_11") (pintype "passive"))
      (node (ref "U3") (pin "15") (pinfunction "GND_15") (pintype "passive"))
    )
    (net (code "33") (name "Net-(U1-SER)") (class "Default")
      (node (ref "U1") (pin "12") (pinfunction "SER_12") (pintype "passive"))
      (node (ref "U2") (pin "14") (pinfunction "QH_14") (pintype "passive"))
    )
    (net (code "34") (name "Net-(U2-SER)") (class "Default")
      (node (ref "U2") (pin "12") (pinfunction "SER_12") (pintype "passive"))
      (node (ref "U3") (pin "14") (pinfunction "QH_14") (pintype "passive"))
    )
    (net (code "35") (name "unconnected-(SW1-Pad1)") (class "Default")
      (node (ref "SW1") (pin "1") (pinfunction "1_1") (pintype "passive+no_connect"))
    )
    (net (code "36") (name "unconnected-(SW1-Pad4)") (class "Default")
      (node (ref "SW1") (pin "4") (pinfunction "4_4") (pintype "passive+no_connect"))
    )
    (net (code "37") (name "unconnected-(SW2-Pad1)") (class "Default")
      (node (ref "SW2") (pin "1") (pinfunction "1_1") (pintype "passive+no_connect"))
    )
    (net (code "38") (name "unconnected-(SW2-Pad4)") (class "Default")
      (node (ref "SW2") (pin "4") (pinfunction "4_4") (pintype "passive+no_connect"))
    )
    (net (code "39") (name "unconnected-(SW3-Pad1)") (class "Default")
      (node (ref "SW3") (pin "1") (pinfunction "1_1") (pintype "passive+no_connect"))
    )
    (net (code "40") (name "unconnected-(SW3-Pad4)") (class "Default")
      (node (ref "SW3") (pin "4") (pinfunction "4_4") (pintype "passive+no_connect"))
    )
    (net (code "41") (name "unconnected-(SW4-Pad1)") (class "Default")
      (node (ref "SW4") (pin "1") (pinfunction "1_1") (pintype "passive+no_connect"))
    )
    (net (code "42") (name "unconnected-(SW4-Pad4)") (class "Default")
      (node (ref "SW4") (pin "4") (pinfunction "4_4") (pintype "passive+no_connect"))
    )
    (net (code "43") (name "unconnected-(SW5-Pad1)") (class "Default")
      (node (ref "SW5") (pin "1") (pinfunction "1_1") (pintype "passive+no_connect"))
    )
    (net (code "44") (name "unconnected-(SW5-Pad4)") (class "Default")
      (node (ref "SW5") (pin "4") (pinfunction "4_4") (pintype "passive+no_connect"))
    )
    (net (code "45") (name "unconnected-(SW6-Pad1)") (class "Default")
      (node (ref "SW6") (pin "1") (pinfunction "1_1") (pintype "passive+no_connect"))
    )
    (net (code "46") (name "unconnected-(SW6-Pad4)") (class "Default")
      (node (ref "SW6") (pin "4") (pinfunction "4_4") (pintype "passive+no_connect"))
    )
    (net (code "47") (name "unconnected-(SW7-Pad1)") (class "Default")
      (node (ref "SW7") (pin "1") (pinfunction "1_1") (pintype "passive+no_connect"))
    )
    (net (code "48") (name "unconnected-(SW7-Pad4)") (class "Default")
      (node (ref "SW7") (pin "4") (pinfunction "4_4") (pintype "passive+no_connect"))
    )
    (net (code "49") (name "unconnected-(SW8-Pad1)") (class "Default")
      (node (ref "SW8") (pin "1") (pinfunction "1_1") (pintype "passive+no_connect"))
    )
    (net (code "50") (name "unconnected-(SW8-Pad4)") (class "Default")
      (node (ref "SW8") (pin "4") (pinfunction "4_4") (pintype "passive+no_connect"))
    )
    (net (code "51") (name "unconnected-(SW9-Pad1)") (class "Default")
      (node (ref "SW9") (pin "1") (pinfunction "1_1") (pintype "passive+no_connect"))
    )
    (net (code "52") (name "unconnected-(SW9-Pad4)") (class "Default")
      (node (ref "SW9") (pin "4") (pinfunction "4_4") (pintype "passive+no_connect"))
    )
    (net (code "53") (name "unconnected-(SW10-Pad1)") (class "Default")
      (node (ref "SW10") (pin "1") (pinfunction "1_1") (pintype "passive+no_connect"))
    )
    (net (code "54") (name "unconnected-(SW10-Pad4)") (class "Default")
      (node (ref "SW10") (pin "4") (pinfunction "4_4") (pintype "passive+no_connect"))
    )
    (net (code "55") (name "unconnected-(SW11-Pad1)") (class "Default")
      (node (ref "SW11") (pin "1") (pinfunction "1_1") (pintype "passive+no_connect"))
    )
    (net (code "56") (name "unconnected-(SW11-Pad4)") (class "Default")
      (node (ref "SW11") (pin "4") (pinfunction "4_4") (pintype "passive+no_connect"))
    )
    (net (code "57") (name "unconnected-(SW12-Pad1)") (class "Default")
      (node (ref "SW12") (pin "1") (pinfunction "1_1") (pintype "passive+no_connect"))
    )
    (net (code "58") (name "unconnected-(SW12-Pad4)") (class "Default")
      (node (ref "SW12") (pin "4") (pinfunction "4_4") (pintype "passive+no_connect"))
    )
    (net (code "59") (name "unconnected-(SW13-Pad1)") (class "Default")
      (node (ref "SW13") (pin "1") (pinfunction "1_1") (pintype "passive+no_connect"))
    )
    (net (code "60") (name "unconnected-(SW13-Pad4)") (class "Default")
      (node (ref "SW13") (pin "4") (pinfunction "4_4") (pintype "passive+no_connect"))
    )
    (net (code "61") (name "unconnected-(SW14-Pad1)") (class "Default")
      (node (ref "SW14") (pin "1") (pinfunction "1_1") (pintype "passive+no_connect"))
    )
    (net (code "62") (name "unconnected-(SW14-Pad4)") (class "Default")
      (node (ref "SW14") (pin "4") (pinfunction "4_4") (pintype "passive+no_connect"))
    )
    (net (code "63") (name "unconnected-(SW15-Pad1)") (class "Default")
      (node (ref "SW15") (pin "1") (pinfunction "1_1") (pintype "passive+no_connect"))
    )
    (net (code "64") (name "unconnected-(SW15-Pad4)") (class "Default")
      (node (ref "SW15") (pin "4") (pinfunction "4_4") (pintype "passive+no_connect"))
    )
    (net (code "65") (name "unconnected-(SW16-Pad1)") (class "Default")
      (node (ref "SW16") (pin "1") (pinfunction "1_1") (pintype "passive+no_connect"))
    )
    (net (code "66") (name "unconnected-(SW16-Pad4)") (class "Default")
      (node (ref "SW16") (pin "4") (pinfunction "4_4") (pintype "passive+no_connect"))
    )
    (net (code "67") (name "unconnected-(SW17-Pad1)") (class "Default")
      (node (ref "SW17") (pin "1") (pinfunction "1_1") (pintype "passive+no_connect"))
    )
    (net (code "68") (name "unconnected-(SW17-Pad4)") (class "Default")
      (node (ref "SW17") (pin "4") (pinfunction "4_4") (pintype "passive+no_connect"))
    )
    (net (code "69") (name "unconnected-(SW18-Pad1)") (class "Default")
      (node (ref "SW18") (pin "1") (pinfunction "1_1") (pintype "passive+no_connect"))
    )
    (net (code "70") (name "unconnected-(SW18-Pad4)") (class "Default")
      (node (ref "SW18") (pin "4") (pinfunction "4_4") (pintype "passive+no_connect"))
    )
    (net (code "71") (name "unconnected-(SW19-Pad1)") (class "Default")
      (node (ref "SW19") (pin "1") (pinfunction "1_1") (pintype "passive+no_connect"))
    )
    (net (code "72") (name "unconnected-(SW19-Pad4)") (class "Default")
      (node (ref "SW19") (pin "4") (pinfunction "4_4") (pintype "passive+no_connect"))
    )
    (net (code "73") (name "unconnected-(SW20-Pad1)") (class "Default")
      (node (ref "SW20") (pin "1") (pinfunction "1_1") (pintype "passive+no_connect"))
    )
    (net (code "74") (name "unconnected-(SW20-Pad4)") (class "Default")
      (node (ref "SW20") (pin "4") (pinfunction "4_4") (pintype "passive+no_connect"))
    )
    (net (code "75") (name "unconnected-(SW21-Pad1)") (class "Default")
      (node (ref "SW21") (pin "1") (pinfunction "1_1") (pintype "passive+no_connect"))
    )
    (net (code "76") (name "unconnected-(SW21-Pad4)") (class "Default")
      (node (ref "SW21") (pin "4") (pinfunction "4_4") (pintype "passive+no_connect"))
    )
    (net (code "77") (name "unconnected-(SW22-Pad1)") (class "Default")
      (node (ref "SW22") (pin "1") (pinfunction "1_1") (pintype "passive+no_connect"))
    )
    (net (code "78") (name "unconnected-(SW22-Pad4)") (class "Default")
      (node (ref "SW22") (pin "4") (pinfunction "4_4") (pintype "passive+no_connect"))
    )
    (net (code "79") (name "unconnected-(SW23-Pad1)") (class "Default")
      (node (ref "SW23") (pin "1") (pinfunction "1_1") (pintype "passive+no_connect"))
    )
    (net (code "80") (name "unconnected-(SW23-Pad4)") (class "Default")
      (node (ref "SW23") (pin "4") (pinfunction "4_4") (pintype "passive+no_connect"))
    )
    (net (code "81") (name "unconnected-(SW24-Pad1)") (class "Default")
      (node (ref "SW24") (pin "1") (pinfunction "1_1") (pintype "passive+no_connect"))
    )
    (net (code "82") (name "unconnected-(SW24-Pad4)") (class "Default")
      (node (ref "SW24") (pin "4") (pinfunction "4_4") (pintype "passive+no_connect"))
    )
    (net (code "83") (name "unconnected-(U1-CLK{slash}INH-Pad11)") (class "Default")
      (node (ref "U1") (pin "11") (pinfunction "CLK/INH_11") (pintype "passive"))
    )
    (net (code "84") (name "unconnected-(U3-SER-Pad12)") (class "Default")
      (node (ref "U3") (pin "12") (pinfunction "SER_12") (pintype "passive"))
    )
  )
)
